# tick-wifi-mk-1_2.net
KiCad netlist of a schematic drawn in EAGLE
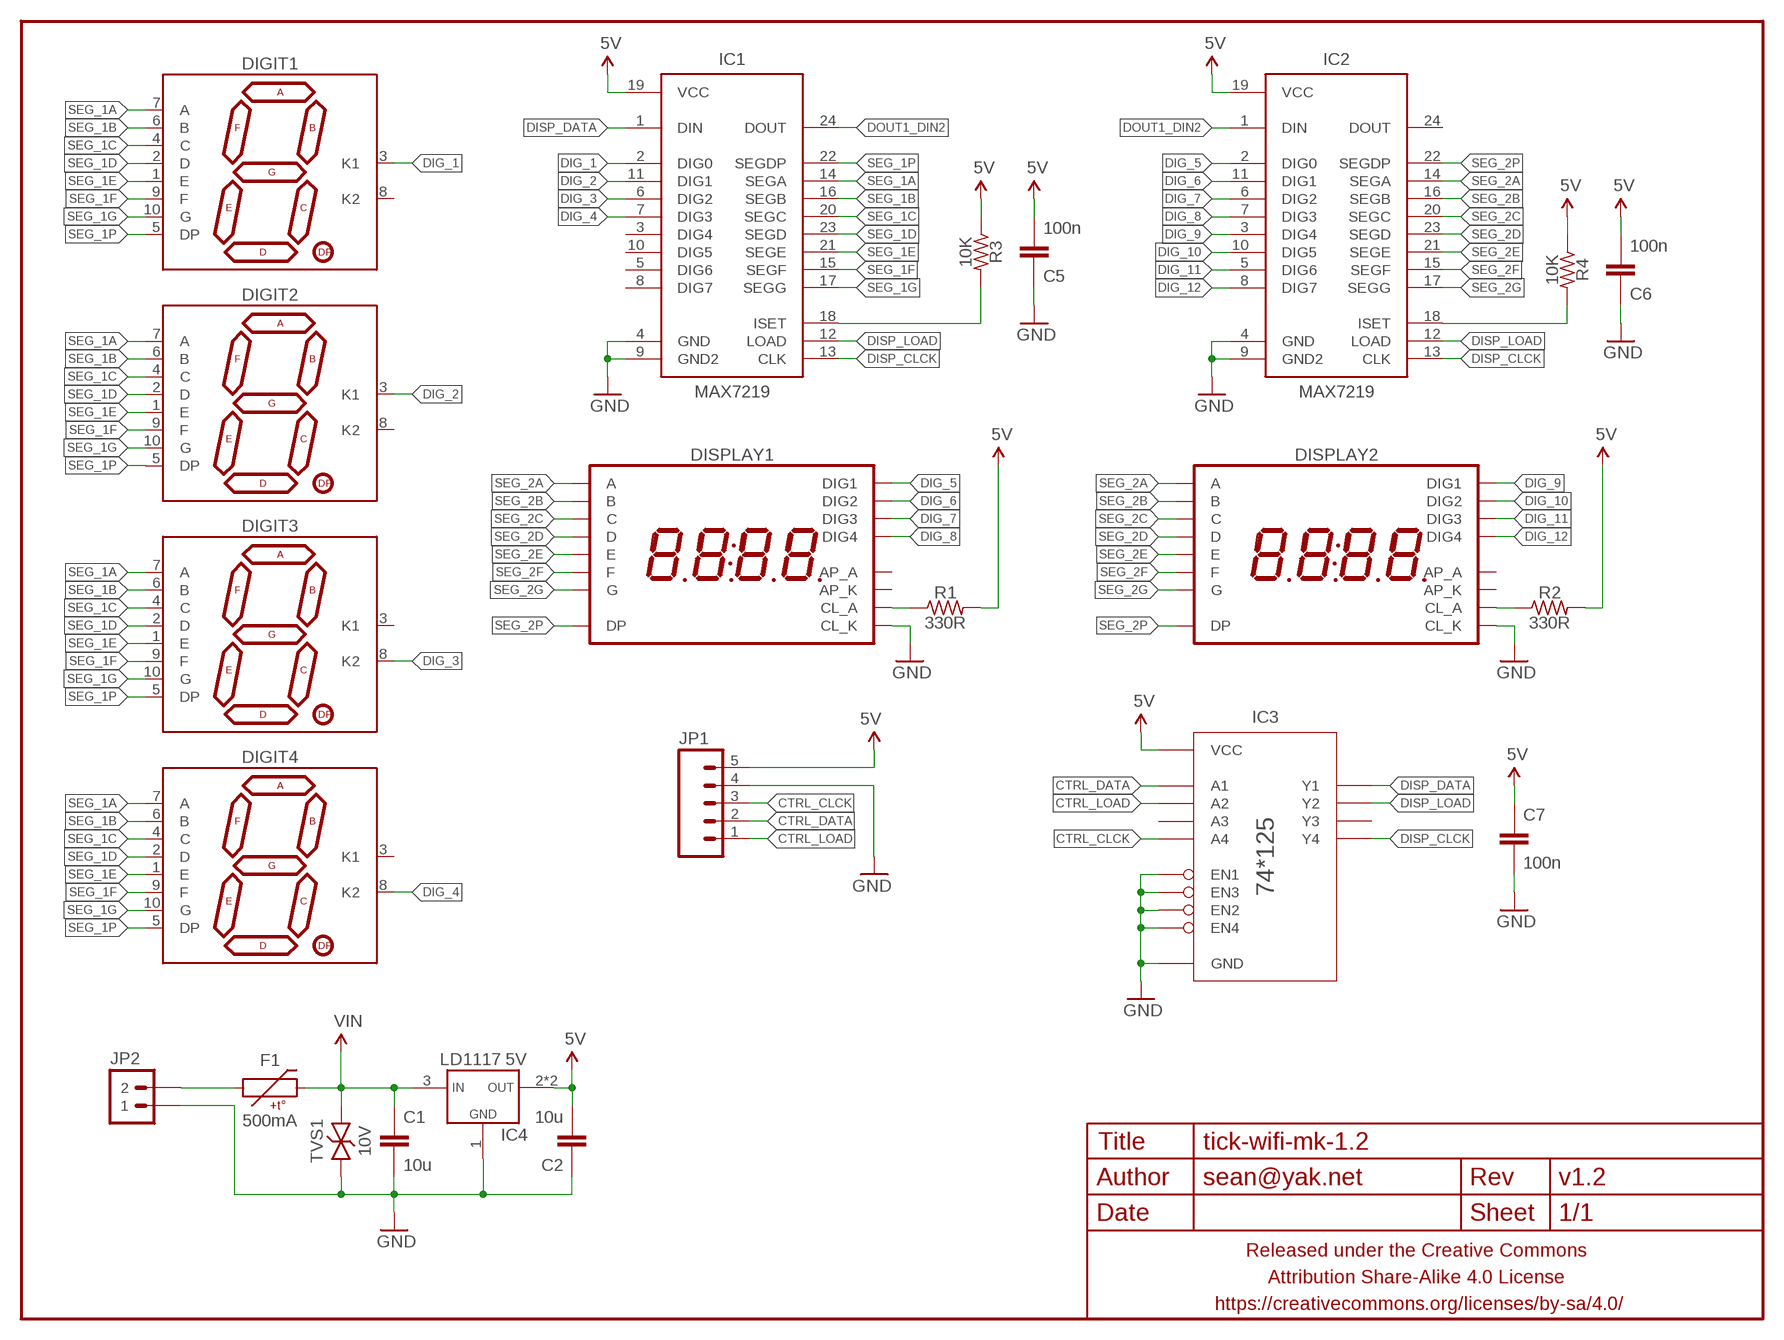
[diagram p0: schematic, sheet 1]

(export (version "E")
  (design (tool "Eeschema 10.0.6"))
  (components
    (comp (ref "C1")
      (value "10u")
      (footprint "eagle-import:C1210")
      (libsource (lib "eagle-import") (part "CAPACITOR-CERAMICC1210"))
    )
    (comp (ref "C2")
      (value "10u")
      (footprint "eagle-import:C1210")
      (libsource (lib "eagle-import") (part "CAPACITOR-CERAMICC1210"))
    )
    (comp (ref "C5")
      (value "100n")
      (footprint "eagle-import:C0603")
      (libsource (lib "eagle-import") (part "CAPACITOR-CERAMICC0603"))
    )
    (comp (ref "C6")
      (value "100n")
      (footprint "eagle-import:C0603")
      (libsource (lib "eagle-import") (part "CAPACITOR-CERAMICC0603"))
    )
    (comp (ref "C7")
      (value "100n")
      (footprint "eagle-import:C0603")
      (libsource (lib "eagle-import") (part "CAPACITOR-CERAMICC0603"))
    )
    (comp (ref "DIGIT1")
      (value "7SEG_1DIGPTH-25.4MM-BARE")
      (footprint "eagle-import:7SEG_1DIG_25.4MM_NOSILK")
      (libsource (lib "eagle-import") (part "7SEG_1DIGPTH-25.4MM-BARE"))
    )
    (comp (ref "DIGIT2")
      (value "7SEG_1DIGPTH-25.4MM-BARE")
      (footprint "eagle-import:7SEG_1DIG_25.4MM_NOSILK")
      (libsource (lib "eagle-import") (part "7SEG_1DIGPTH-25.4MM-BARE"))
    )
    (comp (ref "DIGIT3")
      (value "7SEG_1DIGPTH-25.4MM-BARE")
      (footprint "eagle-import:7SEG_1DIG_25.4MM_NOSILK")
      (libsource (lib "eagle-import") (part "7SEG_1DIGPTH-25.4MM-BARE"))
    )
    (comp (ref "DIGIT4")
      (value "7SEG_1DIGPTH-25.4MM-BARE")
      (footprint "eagle-import:7SEG_1DIG_25.4MM_NOSILK")
      (libsource (lib "eagle-import") (part "7SEG_1DIGPTH-25.4MM-BARE"))
    )
    (comp (ref "DISPLAY1")
      (value "7SEG_4DIGIT_COLON_APOS")
      (footprint "eagle-import:7SEG_4DIG_10MM")
      (libsource (lib "eagle-import") (part "7SEG_4DIGIT_COLON_APOS"))
    )
    (comp (ref "DISPLAY2")
      (value "7SEG_4DIGIT_COLON_APOS")
      (footprint "eagle-import:7SEG_4DIG_10MM")
      (libsource (lib "eagle-import") (part "7SEG_4DIGIT_COLON_APOS"))
    )
    (comp (ref "F1")
      (value "500mA")
      (footprint "eagle-import:PTC-1210")
      (libsource (lib "eagle-import") (part "PTCPTC-1210"))
    )
    (comp (ref "FRAME1")
      (value "FRAME-LETTERNO_PACKAGE")
      (footprint "eagle-import:DUMMY")
      (fields (field (name "DESIGNER") "sean@yak.net") (field (name "VERSION") "v1.2"))
      (libsource (lib "eagle-import") (part "FRAME-LETTERNO_PACKAGE"))
    )
    (comp (ref "IC1")
      (value "MAX7219")
      (footprint "eagle-import:SO24W")
      (libsource (lib "eagle-import") (part "MAX7219SOIC-W"))
    )
    (comp (ref "IC2")
      (value "MAX7219")
      (footprint "eagle-import:SO24W")
      (libsource (lib "eagle-import") (part "MAX7219SOIC-W"))
    )
    (comp (ref "IC3")
      (value "74HC125")
      (footprint "eagle-import:SO14")
      (libsource (lib "eagle-import") (part "74125SOIC14"))
    )
    (comp (ref "IC4")
      (value "LD1117 5V")
      (footprint "eagle-import:SOT223")
      (libsource (lib "eagle-import") (part "VREG_1117SOT223"))
    )
    (comp (ref "JP1")
      (value "M05PTH-CENTERED")
      (footprint "eagle-import:1X05_PTH_CENTERED")
      (libsource (lib "eagle-import") (part "M05PTH-CENTERED"))
    )
    (comp (ref "JP2")
      (value "M02PTH-CENTERED-R+")
      (footprint "eagle-import:1X02-CENTER-R+")
      (libsource (lib "eagle-import") (part "M02PTH-CENTERED-R+"))
    )
    (comp (ref "R1")
      (value "330R")
      (footprint "eagle-import:R0603")
      (libsource (lib "eagle-import") (part "RESISTORR0603"))
    )
    (comp (ref "R2")
      (value "330R")
      (footprint "eagle-import:R0603")
      (libsource (lib "eagle-import") (part "RESISTORR0603"))
    )
    (comp (ref "R3")
      (value "10K")
      (footprint "eagle-import:R0603")
      (libsource (lib "eagle-import") (part "RESISTORR0603"))
    )
    (comp (ref "R4")
      (value "10K")
      (footprint "eagle-import:R0603")
      (libsource (lib "eagle-import") (part "RESISTORR0603"))
    )
    (comp (ref "TVS1")
      (value "10V")
      (footprint "eagle-import:SMA-DIODE-TVS-BIDIR")
      (libsource (lib "eagle-import") (part "TVSSMA"))
    )
  )
  (nets
    (net (code "1") (name "5V") (class "Default")
      (node (ref "C2") (pin "2") (pinfunction "2_2") (pintype "passive"))
      (node (ref "C5") (pin "2") (pinfunction "2_2") (pintype "passive"))
      (node (ref "C6") (pin "2") (pinfunction "2_2") (pintype "passive"))
      (node (ref "C7") (pin "1") (pinfunction "1_1") (pintype "passive"))
      (node (ref "IC1") (pin "19") (pinfunction "VCC_19") (pintype "bidirectional"))
      (node (ref "IC2") (pin "19") (pinfunction "VCC_19") (pintype "bidirectional"))
      (node (ref "IC3") (pin "14") (pinfunction "VCC_14") (pintype "bidirectional"))
      (node (ref "IC4") (pin "2") (pinfunction "VOUT_2") (pintype "bidirectional"))
      (node (ref "IC4") (pin "4") (pinfunction "VOUT_4") (pintype "bidirectional"))
      (node (ref "JP1") (pin "5") (pinfunction "5_5") (pintype "passive"))
      (node (ref "R1") (pin "2") (pinfunction "2_2") (pintype "passive"))
      (node (ref "R2") (pin "2") (pinfunction "2_2") (pintype "passive"))
      (node (ref "R3") (pin "1") (pinfunction "1_1") (pintype "passive"))
      (node (ref "R4") (pin "1") (pinfunction "1_1") (pintype "passive"))
    )
    (net (code "2") (name "CTRL_CLCK") (class "Default")
      (node (ref "IC3") (pin "12") (pinfunction "A4_12") (pintype "bidirectional"))
      (node (ref "JP1") (pin "3") (pinfunction "3_3") (pintype "passive"))
    )
    (net (code "3") (name "CTRL_DATA") (class "Default")
      (node (ref "IC3") (pin "2") (pinfunction "A1_2") (pintype "bidirectional"))
      (node (ref "JP1") (pin "2") (pinfunction "2_2") (pintype "passive"))
    )
    (net (code "4") (name "CTRL_LOAD") (class "Default")
      (node (ref "IC3") (pin "5") (pinfunction "A2_5") (pintype "bidirectional"))
      (node (ref "JP1") (pin "1") (pinfunction "1_1") (pintype "passive"))
    )
    (net (code "5") (name "DIG_1") (class "Default")
      (node (ref "DIGIT1") (pin "3") (pinfunction "K1_3") (pintype "bidirectional"))
      (node (ref "IC1") (pin "2") (pinfunction "DIG0_2") (pintype "bidirectional"))
    )
    (net (code "6") (name "DIG_2") (class "Default")
      (node (ref "DIGIT2") (pin "3") (pinfunction "K1_3") (pintype "bidirectional"))
      (node (ref "IC1") (pin "11") (pinfunction "DIG1_11") (pintype "bidirectional"))
    )
    (net (code "7") (name "DIG_3") (class "Default")
      (node (ref "DIGIT3") (pin "8") (pinfunction "K2_8") (pintype "bidirectional"))
      (node (ref "IC1") (pin "6") (pinfunction "DIG2_6") (pintype "bidirectional"))
    )
    (net (code "8") (name "DIG_4") (class "Default")
      (node (ref "DIGIT4") (pin "8") (pinfunction "K2_8") (pintype "bidirectional"))
      (node (ref "IC1") (pin "7") (pinfunction "DIG3_7") (pintype "bidirectional"))
    )
    (net (code "9") (name "DIG_5") (class "Default")
      (node (ref "DISPLAY1") (pin "1") (pinfunction "DIG1_1") (pintype "passive"))
      (node (ref "IC2") (pin "2") (pinfunction "DIG0_2") (pintype "bidirectional"))
    )
    (net (code "10") (name "DIG_6") (class "Default")
      (node (ref "DISPLAY1") (pin "2") (pinfunction "DIG2_2") (pintype "passive"))
      (node (ref "IC2") (pin "11") (pinfunction "DIG1_11") (pintype "bidirectional"))
    )
    (net (code "11") (name "DIG_7") (class "Default")
      (node (ref "DISPLAY1") (pin "6") (pinfunction "DIG3_6") (pintype "passive"))
      (node (ref "IC2") (pin "6") (pinfunction "DIG2_6") (pintype "bidirectional"))
    )
    (net (code "12") (name "DIG_8") (class "Default")
      (node (ref "DISPLAY1") (pin "8") (pinfunction "DIG4_8") (pintype "passive"))
      (node (ref "IC2") (pin "7") (pinfunction "DIG3_7") (pintype "bidirectional"))
    )
    (net (code "13") (name "DIG_9") (class "Default")
      (node (ref "DISPLAY2") (pin "1") (pinfunction "DIG1_1") (pintype "passive"))
      (node (ref "IC2") (pin "3") (pinfunction "DIG4_3") (pintype "bidirectional"))
    )
    (net (code "14") (name "DIG_10") (class "Default")
      (node (ref "DISPLAY2") (pin "2") (pinfunction "DIG2_2") (pintype "passive"))
      (node (ref "IC2") (pin "10") (pinfunction "DIG5_10") (pintype "bidirectional"))
    )
    (net (code "15") (name "DIG_11") (class "Default")
      (node (ref "DISPLAY2") (pin "6") (pinfunction "DIG3_6") (pintype "passive"))
      (node (ref "IC2") (pin "5") (pinfunction "DIG6_5") (pintype "bidirectional"))
    )
    (net (code "16") (name "DIG_12") (class "Default")
      (node (ref "DISPLAY2") (pin "8") (pinfunction "DIG4_8") (pintype "passive"))
      (node (ref "IC2") (pin "8") (pinfunction "DIG7_8") (pintype "bidirectional"))
    )
    (net (code "17") (name "DISP_CLCK") (class "Default")
      (node (ref "IC1") (pin "13") (pinfunction "CLK_13") (pintype "bidirectional"))
      (node (ref "IC2") (pin "13") (pinfunction "CLK_13") (pintype "bidirectional"))
      (node (ref "IC3") (pin "11") (pinfunction "Y4_11") (pintype "bidirectional"))
    )
    (net (code "18") (name "DISP_DATA") (class "Default")
      (node (ref "IC1") (pin "1") (pinfunction "DIN_1") (pintype "bidirectional"))
      (node (ref "IC3") (pin "3") (pinfunction "Y1_3") (pintype "bidirectional"))
    )
    (net (code "19") (name "DISP_LOAD") (class "Default")
      (node (ref "IC1") (pin "12") (pinfunction "LOAD_12") (pintype "bidirectional"))
      (node (ref "IC2") (pin "12") (pinfunction "LOAD_12") (pintype "bidirectional"))
      (node (ref "IC3") (pin "6") (pinfunction "Y2_6") (pintype "bidirectional"))
    )
    (net (code "20") (name "DOUT1_DIN2") (class "Default")
      (node (ref "IC1") (pin "24") (pinfunction "DOUT_24") (pintype "bidirectional"))
      (node (ref "IC2") (pin "1") (pinfunction "DIN_1") (pintype "bidirectional"))
    )
    (net (code "21") (name "GND") (class "Default")
      (node (ref "C1") (pin "2") (pinfunction "2_2") (pintype "passive"))
      (node (ref "C2") (pin "1") (pinfunction "1_1") (pintype "passive"))
      (node (ref "C5") (pin "1") (pinfunction "1_1") (pintype "passive"))
      (node (ref "C6") (pin "1") (pinfunction "1_1") (pintype "passive"))
      (node (ref "C7") (pin "2") (pinfunction "2_2") (pintype "passive"))
      (node (ref "DISPLAY1") (pin "12") (pinfunction "CL_K_12") (pintype "passive"))
      (node (ref "DISPLAY2") (pin "12") (pinfunction "CL_K_12") (pintype "passive"))
      (node (ref "IC1") (pin "4") (pinfunction "GND_4") (pintype "bidirectional"))
      (node (ref "IC1") (pin "9") (pinfunction "GND2_9") (pintype "bidirectional"))
      (node (ref "IC2") (pin "4") (pinfunction "GND_4") (pintype "bidirectional"))
      (node (ref "IC2") (pin "9") (pinfunction "GND2_9") (pintype "bidirectional"))
      (node (ref "IC3") (pin "1") (pinfunction "EN1_1") (pintype "bidirectional"))
      (node (ref "IC3") (pin "10") (pinfunction "EN3_10") (pintype "bidirectional"))
      (node (ref "IC3") (pin "13") (pinfunction "EN4_13") (pintype "bidirectional"))
      (node (ref "IC3") (pin "4") (pinfunction "EN2_4") (pintype "bidirectional"))
      (node (ref "IC3") (pin "7") (pinfunction "GND_7") (pintype "bidirectional"))
      (node (ref "IC4") (pin "1") (pinfunction "GND_1") (pintype "bidirectional"))
      (node (ref "JP1") (pin "4") (pinfunction "4_4") (pintype "passive"))
      (node (ref "JP2") (pin "1") (pinfunction "1_1") (pintype "passive"))
      (node (ref "TVS1") (pin "1") (pinfunction "1_1") (pintype "passive"))
    )
    (net (code "22") (name "Net-(DISPLAY1-CL_A)") (class "Default")
      (node (ref "DISPLAY1") (pin "4") (pinfunction "CL_A_4") (pintype "passive"))
      (node (ref "R1") (pin "1") (pinfunction "1_1") (pintype "passive"))
    )
    (net (code "23") (name "Net-(DISPLAY2-CL_A)") (class "Default")
      (node (ref "DISPLAY2") (pin "4") (pinfunction "CL_A_4") (pintype "passive"))
      (node (ref "R2") (pin "1") (pinfunction "1_1") (pintype "passive"))
    )
    (net (code "24") (name "Net-(F1-Pad1)") (class "Default")
      (node (ref "F1") (pin "1") (pinfunction "1_1") (pintype "passive"))
      (node (ref "JP2") (pin "2") (pinfunction "2_2") (pintype "passive"))
    )
    (net (code "25") (name "Net-(IC1-ISET)") (class "Default")
      (node (ref "IC1") (pin "18") (pinfunction "ISET_18") (pintype "bidirectional"))
      (node (ref "R3") (pin "2") (pinfunction "2_2") (pintype "passive"))
    )
    (net (code "26") (name "Net-(IC2-ISET)") (class "Default")
      (node (ref "IC2") (pin "18") (pinfunction "ISET_18") (pintype "bidirectional"))
      (node (ref "R4") (pin "2") (pinfunction "2_2") (pintype "passive"))
    )
    (net (code "27") (name "SEG_1A") (class "Default")
      (node (ref "DIGIT1") (pin "7") (pinfunction "A_7") (pintype "bidirectional"))
      (node (ref "DIGIT2") (pin "7") (pinfunction "A_7") (pintype "bidirectional"))
      (node (ref "DIGIT3") (pin "7") (pinfunction "A_7") (pintype "bidirectional"))
      (node (ref "DIGIT4") (pin "7") (pinfunction "A_7") (pintype "bidirectional"))
      (node (ref "IC1") (pin "14") (pinfunction "SEGA_14") (pintype "bidirectional"))
    )
    (net (code "28") (name "SEG_1B") (class "Default")
      (node (ref "DIGIT1") (pin "6") (pinfunction "B_6") (pintype "bidirectional"))
      (node (ref "DIGIT2") (pin "6") (pinfunction "B_6") (pintype "bidirectional"))
      (node (ref "DIGIT3") (pin "6") (pinfunction "B_6") (pintype "bidirectional"))
      (node (ref "DIGIT4") (pin "6") (pinfunction "B_6") (pintype "bidirectional"))
      (node (ref "IC1") (pin "16") (pinfunction "SEGB_16") (pintype "bidirectional"))
    )
    (net (code "29") (name "SEG_1C") (class "Default")
      (node (ref "DIGIT1") (pin "4") (pinfunction "C_4") (pintype "bidirectional"))
      (node (ref "DIGIT2") (pin "4") (pinfunction "C_4") (pintype "bidirectional"))
      (node (ref "DIGIT3") (pin "4") (pinfunction "C_4") (pintype "bidirectional"))
      (node (ref "DIGIT4") (pin "4") (pinfunction "C_4") (pintype "bidirectional"))
      (node (ref "IC1") (pin "20") (pinfunction "SEGC_20") (pintype "bidirectional"))
    )
    (net (code "30") (name "SEG_1D") (class "Default")
      (node (ref "DIGIT1") (pin "2") (pinfunction "D_2") (pintype "bidirectional"))
      (node (ref "DIGIT2") (pin "2") (pinfunction "D_2") (pintype "bidirectional"))
      (node (ref "DIGIT3") (pin "2") (pinfunction "D_2") (pintype "bidirectional"))
      (node (ref "DIGIT4") (pin "2") (pinfunction "D_2") (pintype "bidirectional"))
      (node (ref "IC1") (pin "23") (pinfunction "SEGD_23") (pintype "bidirectional"))
    )
    (net (code "31") (name "SEG_1E") (class "Default")
      (node (ref "DIGIT1") (pin "1") (pinfunction "E_1") (pintype "bidirectional"))
      (node (ref "DIGIT2") (pin "1") (pinfunction "E_1") (pintype "bidirectional"))
      (node (ref "DIGIT3") (pin "1") (pinfunction "E_1") (pintype "bidirectional"))
      (node (ref "DIGIT4") (pin "1") (pinfunction "E_1") (pintype "bidirectional"))
      (node (ref "IC1") (pin "21") (pinfunction "SEGE_21") (pintype "bidirectional"))
    )
    (net (code "32") (name "SEG_1F") (class "Default")
      (node (ref "DIGIT1") (pin "9") (pinfunction "F_9") (pintype "bidirectional"))
      (node (ref "DIGIT2") (pin "9") (pinfunction "F_9") (pintype "bidirectional"))
      (node (ref "DIGIT3") (pin "9") (pinfunction "F_9") (pintype "bidirectional"))
      (node (ref "DIGIT4") (pin "9") (pinfunction "F_9") (pintype "bidirectional"))
      (node (ref "IC1") (pin "15") (pinfunction "SEGF_15") (pintype "bidirectional"))
    )
    (net (code "33") (name "SEG_1G") (class "Default")
      (node (ref "DIGIT1") (pin "10") (pinfunction "G_10") (pintype "bidirectional"))
      (node (ref "DIGIT2") (pin "10") (pinfunction "G_10") (pintype "bidirectional"))
      (node (ref "DIGIT3") (pin "10") (pinfunction "G_10") (pintype "bidirectional"))
      (node (ref "DIGIT4") (pin "10") (pinfunction "G_10") (pintype "bidirectional"))
      (node (ref "IC1") (pin "17") (pinfunction "SEGG_17") (pintype "bidirectional"))
    )
    (net (code "34") (name "SEG_1P") (class "Default")
      (node (ref "DIGIT1") (pin "5") (pinfunction "DP_5") (pintype "bidirectional"))
      (node (ref "DIGIT2") (pin "5") (pinfunction "DP_5") (pintype "bidirectional"))
      (node (ref "DIGIT3") (pin "5") (pinfunction "DP_5") (pintype "bidirectional"))
      (node (ref "DIGIT4") (pin "5") (pinfunction "DP_5") (pintype "bidirectional"))
      (node (ref "IC1") (pin "22") (pinfunction "SEGDP_22") (pintype "bidirectional"))
    )
    (net (code "35") (name "SEG_2A") (class "Default")
      (node (ref "DISPLAY1") (pin "14") (pinfunction "A_14") (pintype "passive"))
      (node (ref "DISPLAY2") (pin "14") (pinfunction "A_14") (pintype "passive"))
      (node (ref "IC2") (pin "14") (pinfunction "SEGA_14") (pintype "bidirectional"))
    )
    (net (code "36") (name "SEG_2B") (class "Default")
      (node (ref "DISPLAY1") (pin "16") (pinfunction "B_16") (pintype "passive"))
      (node (ref "DISPLAY2") (pin "16") (pinfunction "B_16") (pintype "passive"))
      (node (ref "IC2") (pin "16") (pinfunction "SEGB_16") (pintype "bidirectional"))
    )
    (net (code "37") (name "SEG_2C") (class "Default")
      (node (ref "DISPLAY1") (pin "13") (pinfunction "C_13") (pintype "passive"))
      (node (ref "DISPLAY2") (pin "13") (pinfunction "C_13") (pintype "passive"))
      (node (ref "IC2") (pin "20") (pinfunction "SEGC_20") (pintype "bidirectional"))
    )
    (net (code "38") (name "SEG_2D") (class "Default")
      (node (ref "DISPLAY1") (pin "3") (pinfunction "D_3") (pintype "passive"))
      (node (ref "DISPLAY2") (pin "3") (pinfunction "D_3") (pintype "passive"))
      (node (ref "IC2") (pin "23") (pinfunction "SEGD_23") (pintype "bidirectional"))
    )
    (net (code "39") (name "SEG_2E") (class "Default")
      (node (ref "DISPLAY1") (pin "5") (pinfunction "E_5") (pintype "passive"))
      (node (ref "DISPLAY2") (pin "5") (pinfunction "E_5") (pintype "passive"))
      (node (ref "IC2") (pin "21") (pinfunction "SEGE_21") (pintype "bidirectional"))
    )
    (net (code "40") (name "SEG_2F") (class "Default")
      (node (ref "DISPLAY1") (pin "11") (pinfunction "F_11") (pintype "passive"))
      (node (ref "DISPLAY2") (pin "11") (pinfunction "F_11") (pintype "passive"))
      (node (ref "IC2") (pin "15") (pinfunction "SEGF_15") (pintype "bidirectional"))
    )
    (net (code "41") (name "SEG_2G") (class "Default")
      (node (ref "DISPLAY1") (pin "15") (pinfunction "G_15") (pintype "passive"))
      (node (ref "DISPLAY2") (pin "15") (pinfunction "G_15") (pintype "passive"))
      (node (ref "IC2") (pin "17") (pinfunction "SEGG_17") (pintype "bidirectional"))
    )
    (net (code "42") (name "SEG_2P") (class "Default")
      (node (ref "DISPLAY1") (pin "7") (pinfunction "DP_7") (pintype "passive"))
      (node (ref "DISPLAY2") (pin "7") (pinfunction "DP_7") (pintype "passive"))
      (node (ref "IC2") (pin "22") (pinfunction "SEGDP_22") (pintype "bidirectional"))
    )
    (net (code "43") (name "VIN") (class "Default")
      (node (ref "C1") (pin "1") (pinfunction "1_1") (pintype "passive"))
      (node (ref "F1") (pin "2") (pinfunction "2_2") (pintype "passive"))
      (node (ref "IC4") (pin "3") (pinfunction "VIN_3") (pintype "bidirectional"))
      (node (ref "TVS1") (pin "2") (pinfunction "2_2") (pintype "passive"))
    )
    (net (code "44") (name "unconnected-(DIGIT1-K2-Pad8)") (class "Default")
      (node (ref "DIGIT1") (pin "8") (pinfunction "K2_8") (pintype "bidirectional"))
    )
    (net (code "45") (name "unconnected-(DIGIT2-K2-Pad8)") (class "Default")
      (node (ref "DIGIT2") (pin "8") (pinfunction "K2_8") (pintype "bidirectional"))
    )
    (net (code "46") (name "unconnected-(DIGIT3-K1-Pad3)") (class "Default")
      (node (ref "DIGIT3") (pin "3") (pinfunction "K1_3") (pintype "bidirectional"))
    )
    (net (code "47") (name "unconnected-(DIGIT4-K1-Pad3)") (class "Default")
      (node (ref "DIGIT4") (pin "3") (pinfunction "K1_3") (pintype "bidirectional"))
    )
    (net (code "48") (name "unconnected-(DISPLAY1-AP_A-Pad10)") (class "Default")
      (node (ref "DISPLAY1") (pin "10") (pinfunction "AP_A_10") (pintype "bidirectional"))
    )
    (net (code "49") (name "unconnected-(DISPLAY1-AP_K-Pad9)") (class "Default")
      (node (ref "DISPLAY1") (pin "9") (pinfunction "AP_K_9") (pintype "bidirectional"))
    )
    (net (code "50") (name "unconnected-(DISPLAY2-AP_A-Pad10)") (class "Default")
      (node (ref "DISPLAY2") (pin "10") (pinfunction "AP_A_10") (pintype "bidirectional"))
    )
    (net (code "51") (name "unconnected-(DISPLAY2-AP_K-Pad9)") (class "Default")
      (node (ref "DISPLAY2") (pin "9") (pinfunction "AP_K_9") (pintype "bidirectional"))
    )
    (net (code "52") (name "unconnected-(IC1-DIG4-Pad3)") (class "Default")
      (node (ref "IC1") (pin "3") (pinfunction "DIG4_3") (pintype "bidirectional"))
    )
    (net (code "53") (name "unconnected-(IC1-DIG5-Pad10)") (class "Default")
      (node (ref "IC1") (pin "10") (pinfunction "DIG5_10") (pintype "bidirectional"))
    )
    (net (code "54") (name "unconnected-(IC1-DIG6-Pad5)") (class "Default")
      (node (ref "IC1") (pin "5") (pinfunction "DIG6_5") (pintype "bidirectional"))
    )
    (net (code "55") (name "unconnected-(IC1-DIG7-Pad8)") (class "Default")
      (node (ref "IC1") (pin "8") (pinfunction "DIG7_8") (pintype "bidirectional"))
    )
    (net (code "56") (name "unconnected-(IC2-DOUT-Pad24)") (class "Default")
      (node (ref "IC2") (pin "24") (pinfunction "DOUT_24") (pintype "bidirectional"))
    )
    (net (code "57") (name "unconnected-(IC3-A3-Pad9)") (class "Default")
      (node (ref "IC3") (pin "9") (pinfunction "A3_9") (pintype "bidirectional"))
    )
    (net (code "58") (name "unconnected-(IC3-Y3-Pad8)") (class "Default")
      (node (ref "IC3") (pin "8") (pinfunction "Y3_8") (pintype "bidirectional"))
    )
  )
)
